# SCHEasyEda.net
KiCad netlist of a schematic drawn in EasyEDA
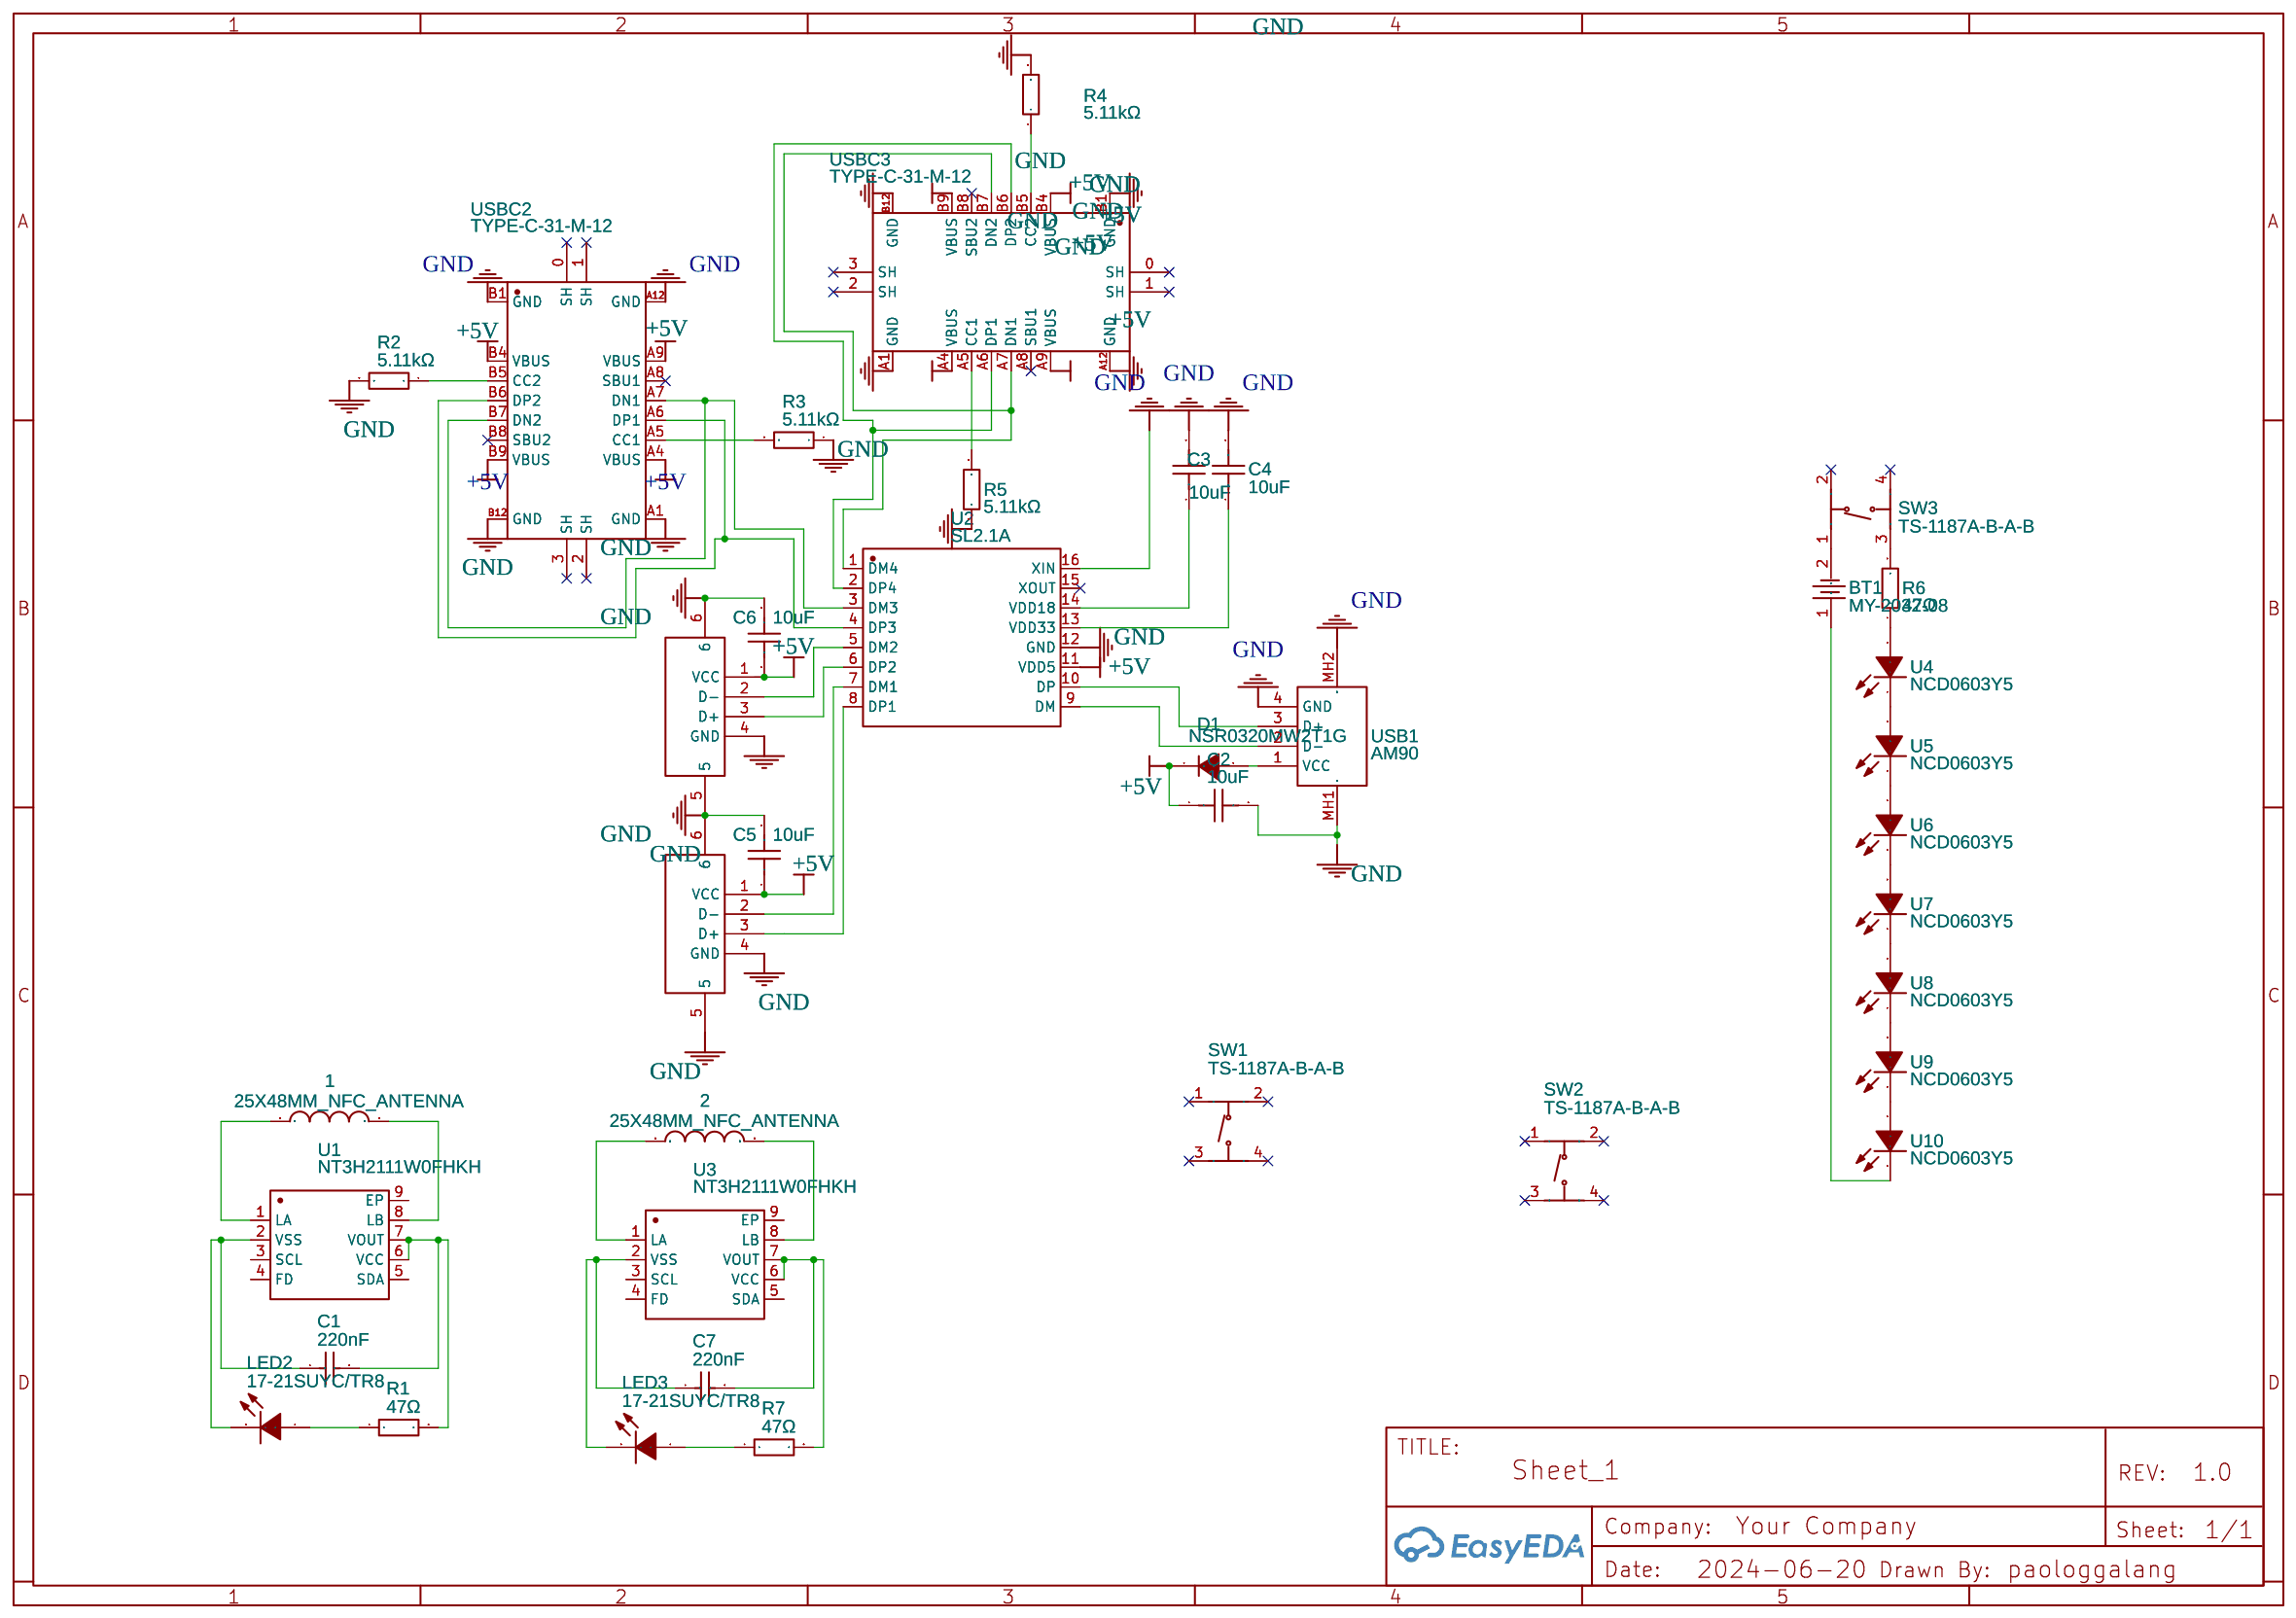
[diagram p0: schematic sheet]

(export (version "E")
  (design (tool "Eeschema 10.0.6"))
  (components
    (comp (ref "1") (value "25X48MM_NFC_ANTENNA") (libsource (lib "") (part "25X48MM_NFC_ANTENNA")))
    (comp (ref "2") (value "25X48MM_NFC_ANTENNA") (libsource (lib "") (part "25X48MM_NFC_ANTENNA")))
    (comp (ref "BT1")
      (value "MY-2032-08")
      (fields (field (name "Manufacturer") "MYOUNG(美阳)"))
      (libsource (lib "") (part "MY-2032-08"))
    )
    (comp (ref "C1")
      (value "220nF")
      (fields
        (field (name "Manufacturer Part") "CL10B224KA8NNNC")
        (field (name "Manufacturer") "SAMSUNG(三星)")
      )
      (libsource (lib "") (part "CL10B224KA8NNNC"))
    )
    (comp (ref "C2")
      (value "10uF")
      (fields
        (field (name "Manufacturer Part") "CL10A106KP8NNNC")
        (field (name "Manufacturer") "SAMSUNG(三星)")
      )
      (libsource (lib "") (part "CL10A106KP8NNNC_1"))
    )
    (comp (ref "C3")
      (value "10uF")
      (fields
        (field (name "Manufacturer Part") "CL10A106KP8NNNC")
        (field (name "Manufacturer") "SAMSUNG(三星)")
      )
      (libsource (lib "") (part "CL10A106KP8NNNC"))
    )
    (comp (ref "C4")
      (value "10uF")
      (fields
        (field (name "Manufacturer Part") "CL10A106KP8NNNC")
        (field (name "Manufacturer") "SAMSUNG(三星)")
      )
      (libsource (lib "") (part "CL10A106KP8NNNC"))
    )
    (comp (ref "C5")
      (value "10uF")
      (fields
        (field (name "Manufacturer Part") "CL10A106KP8NNNC")
        (field (name "Manufacturer") "SAMSUNG(三星)")
      )
      (libsource (lib "") (part "CL10A106KP8NNNC"))
    )
    (comp (ref "C6")
      (value "10uF")
      (fields
        (field (name "Manufacturer Part") "CL10A106KP8NNNC")
        (field (name "Manufacturer") "SAMSUNG(三星)")
      )
      (libsource (lib "") (part "CL10A106KP8NNNC"))
    )
    (comp (ref "C7")
      (value "220nF")
      (fields
        (field (name "Manufacturer Part") "CL10B224KA8NNNC")
        (field (name "Manufacturer") "SAMSUNG(三星)")
      )
      (libsource (lib "") (part "CL10B224KA8NNNC"))
    )
    (comp (ref "D1")
      (value "NSR0320MW2T1G")
      (fields (field (name "Manufacturer") "onsemi(安森美)"))
      (libsource (lib "") (part "NSR0320MW2T1G"))
    )
    (comp (ref "LED2")
      (value "17-21SUYC/TR8")
      (fields (field (name "Manufacturer Part") "KT-0805黄灯") (field (name "Manufacturer") "KENTO"))
      (libsource (lib "") (part "17-21SUYC/TR8"))
    )
    (comp (ref "LED3")
      (value "17-21SUYC/TR8")
      (fields (field (name "Manufacturer Part") "KT-0805黄灯") (field (name "Manufacturer") "KENTO"))
      (libsource (lib "") (part "17-21SUYC/TR8"))
    )
    (comp (ref "R1")
      (value "47Ω")
      (fields
        (field (name "Manufacturer Part") "0603WAF470JT5E")
        (field (name "Manufacturer") "UNI-ROYAL(厚声)")
      )
      (libsource (lib "") (part "0603WAF470JT5E"))
    )
    (comp (ref "R2")
      (value "5.11kΩ")
      (fields
        (field (name "Manufacturer Part") "RMC12065.11K1%N")
        (field (name "Manufacturer") "Tyohm(幸亚电阻)")
      )
      (libsource (lib "") (part "RMC12065.11K1%N"))
    )
    (comp (ref "R3")
      (value "5.11kΩ")
      (fields
        (field (name "Manufacturer Part") "RMC12065.11K1%N")
        (field (name "Manufacturer") "Tyohm(幸亚电阻)")
      )
      (libsource (lib "") (part "RMC12065.11K1%N"))
    )
    (comp (ref "R4")
      (value "5.11kΩ")
      (fields
        (field (name "Manufacturer Part") "RMC12065.11K1%N")
        (field (name "Manufacturer") "Tyohm(幸亚电阻)")
      )
      (libsource (lib "") (part "RMC12065.11K1%N_1"))
    )
    (comp (ref "R5")
      (value "5.11kΩ")
      (fields
        (field (name "Manufacturer Part") "RMC12065.11K1%N")
        (field (name "Manufacturer") "Tyohm(幸亚电阻)")
      )
      (libsource (lib "") (part "RMC12065.11K1%N_1"))
    )
    (comp (ref "R6")
      (value "47Ω")
      (fields
        (field (name "Manufacturer Part") "0603WAF470JT5E")
        (field (name "Manufacturer") "UNI-ROYAL(厚声)")
      )
      (libsource (lib "") (part "0603WAF470JT5E_1"))
    )
    (comp (ref "R7")
      (value "47Ω")
      (fields
        (field (name "Manufacturer Part") "0603WAF470JT5E")
        (field (name "Manufacturer") "UNI-ROYAL(厚声)")
      )
      (libsource (lib "") (part "0603WAF470JT5E"))
    )
    (comp (ref "SW1")
      (value "TS-1187A-B-A-B")
      (fields (field (name "Manufacturer") "XKB Connectivity(中国星坤)"))
      (libsource (lib "") (part "TS-1187A-B-A-B"))
    )
    (comp (ref "SW2")
      (value "TS-1187A-B-A-B")
      (fields (field (name "Manufacturer") "XKB Connectivity(中国星坤)"))
      (libsource (lib "") (part "TS-1187A-B-A-B"))
    )
    (comp (ref "SW3")
      (value "TS-1187A-B-A-B")
      (fields (field (name "Manufacturer") "XKB Connectivity(中国星坤)"))
      (libsource (lib "") (part "TS-1187A-B-A-B_1"))
    )
    (comp (ref "U1")
      (value "NT3H2111W0FHKH")
      (fields (field (name "Manufacturer") "NXP(恩智浦)"))
      (libsource (lib "") (part "NT3H2111W0FHKH"))
    )
    (comp (ref "U2")
      (value "SL2.1A")
      (fields (field (name "Manufacturer") "CoreChips(和芯润德)"))
      (libsource (lib "") (part "SL2.1A"))
    )
    (comp (ref "U3")
      (value "NT3H2111W0FHKH")
      (fields (field (name "Manufacturer") "NXP(恩智浦)"))
      (libsource (lib "") (part "NT3H2111W0FHKH"))
    )
    (comp (ref "U4")
      (value "NCD0603Y5")
      (fields (field (name "Manufacturer") "国星光电"))
      (libsource (lib "") (part "NCD0603Y5"))
    )
    (comp (ref "U5")
      (value "NCD0603Y5")
      (fields (field (name "Manufacturer") "国星光电"))
      (libsource (lib "") (part "NCD0603Y5"))
    )
    (comp (ref "U6")
      (value "NCD0603Y5")
      (fields (field (name "Manufacturer") "国星光电"))
      (libsource (lib "") (part "NCD0603Y5"))
    )
    (comp (ref "U7")
      (value "NCD0603Y5")
      (fields (field (name "Manufacturer") "国星光电"))
      (libsource (lib "") (part "NCD0603Y5"))
    )
    (comp (ref "U8")
      (value "NCD0603Y5")
      (fields (field (name "Manufacturer") "国星光电"))
      (libsource (lib "") (part "NCD0603Y5"))
    )
    (comp (ref "U9")
      (value "NCD0603Y5")
      (fields (field (name "Manufacturer") "国星光电"))
      (libsource (lib "") (part "NCD0603Y5"))
    )
    (comp (ref "U10")
      (value "NCD0603Y5")
      (fields (field (name "Manufacturer") "国星光电"))
      (libsource (lib "") (part "NCD0603Y5"))
    )
    (comp (ref "USB1")
      (value "AM90")
      (fields (field (name "Manufacturer") "SHOU HAN(首韩)"))
      (libsource (lib "") (part "AM90"))
    )
    (comp (ref "USB2")
      (value "USB-AF-90-14.4X13.6-H7.0-DIP")
      (fields (field (name "Manufacturer Part") "903-131A1011D10100") (field (name "Manufacturer") "精拓金"))
      (libsource (lib "") (part "USB-AF-90-14.4X13.6-H7.0-DIP"))
    )
    (comp (ref "USB6")
      (value "USB-AF-90-14.4X13.6-H7.0-DIP")
      (fields (field (name "Manufacturer Part") "903-131A1011D10100") (field (name "Manufacturer") "精拓金"))
      (libsource (lib "") (part "USB-AF-90-14.4X13.6-H7.0-DIP"))
    )
    (comp (ref "USBC2")
      (value "TYPE-C-31-M-12")
      (fields (field (name "Manufacturer") "韩国韩荣"))
      (libsource (lib "") (part "TYPE-C-31-M-12_1"))
    )
    (comp (ref "USBC3")
      (value "TYPE-C-31-M-12")
      (fields (field (name "Manufacturer") "韩国韩荣"))
      (libsource (lib "") (part "TYPE-C-31-M-12"))
    )
  )
  (nets
    (net (code "1") (name "+5V") (class "Default")
      (node (ref "C2") (pin "1") (pinfunction "1_1") (pintype "unspecified"))
      (node (ref "C5") (pin "1") (pinfunction "1_1") (pintype "unspecified"))
      (node (ref "C6") (pin "1") (pinfunction "1_1") (pintype "unspecified"))
      (node (ref "D1") (pin "1") (pinfunction "C_1") (pintype "unspecified"))
      (node (ref "U2") (pin "11") (pinfunction "VDD5_11") (pintype "unspecified"))
      (node (ref "USB2") (pin "1") (pinfunction "VCC_1") (pintype "unspecified"))
      (node (ref "USB6") (pin "1") (pinfunction "VCC_1") (pintype "unspecified"))
      (node (ref "USBC2") (pin "A4") (pinfunction "VBUS_A4") (pintype "unspecified"))
      (node (ref "USBC2") (pin "A9") (pinfunction "VBUS_A9") (pintype "unspecified"))
      (node (ref "USBC2") (pin "B4") (pinfunction "VBUS_B4") (pintype "unspecified"))
      (node (ref "USBC2") (pin "B9") (pinfunction "VBUS_B9") (pintype "unspecified"))
      (node (ref "USBC3") (pin "A4") (pinfunction "VBUS_A4") (pintype "unspecified"))
      (node (ref "USBC3") (pin "A9") (pinfunction "VBUS_A9") (pintype "unspecified"))
      (node (ref "USBC3") (pin "B4") (pinfunction "VBUS_B4") (pintype "unspecified"))
      (node (ref "USBC3") (pin "B9") (pinfunction "VBUS_B9") (pintype "unspecified"))
    )
    (net (code "2") (name "GND") (class "Default")
      (node (ref "C2") (pin "2") (pinfunction "2_2") (pintype "unspecified"))
      (node (ref "C3") (pin "2") (pinfunction "2_2") (pintype "unspecified"))
      (node (ref "C4") (pin "2") (pinfunction "2_2") (pintype "unspecified"))
      (node (ref "C5") (pin "2") (pinfunction "2_2") (pintype "unspecified"))
      (node (ref "C6") (pin "2") (pinfunction "2_2") (pintype "unspecified"))
      (node (ref "R2") (pin "2") (pinfunction "2_2") (pintype "unspecified"))
      (node (ref "R3") (pin "1") (pinfunction "1_1") (pintype "unspecified"))
      (node (ref "R4") (pin "2") (pinfunction "2_2") (pintype "unspecified"))
      (node (ref "R5") (pin "1") (pinfunction "1_1") (pintype "unspecified"))
      (node (ref "U2") (pin "12") (pinfunction "GND_12") (pintype "unspecified"))
      (node (ref "U2") (pin "16") (pinfunction "XIN_16") (pintype "unspecified"))
      (node (ref "USB1") (pin "4") (pinfunction "GND_4") (pintype "input"))
      (node (ref "USB1") (pin "MH1") (pinfunction "MH1_MH1") (pintype "unspecified"))
      (node (ref "USB1") (pin "MH2") (pinfunction "MH2_MH2") (pintype "unspecified"))
      (node (ref "USB2") (pin "4") (pinfunction "GND_4") (pintype "unspecified"))
      (node (ref "USB2") (pin "5") (pinfunction "5_5") (pintype "unspecified"))
      (node (ref "USB2") (pin "6") (pinfunction "6_6") (pintype "unspecified"))
      (node (ref "USB6") (pin "4") (pinfunction "GND_4") (pintype "unspecified"))
      (node (ref "USB6") (pin "5") (pinfunction "5_5") (pintype "unspecified"))
      (node (ref "USB6") (pin "6") (pinfunction "6_6") (pintype "unspecified"))
      (node (ref "USBC2") (pin "A1") (pinfunction "GND_A1") (pintype "unspecified"))
      (node (ref "USBC2") (pin "A12") (pinfunction "GND_A12") (pintype "unspecified"))
      (node (ref "USBC2") (pin "B1") (pinfunction "GND_B1") (pintype "unspecified"))
      (node (ref "USBC2") (pin "B12") (pinfunction "GND_B12") (pintype "unspecified"))
      (node (ref "USBC3") (pin "A1") (pinfunction "GND_A1") (pintype "unspecified"))
      (node (ref "USBC3") (pin "A12") (pinfunction "GND_A12") (pintype "unspecified"))
      (node (ref "USBC3") (pin "B1") (pinfunction "GND_B1") (pintype "unspecified"))
      (node (ref "USBC3") (pin "B12") (pinfunction "GND_B12") (pintype "unspecified"))
    )
    (net (code "3") (name "Net-(D1-A)") (class "Default")
      (node (ref "D1") (pin "2") (pinfunction "A_2") (pintype "unspecified"))
      (node (ref "USB1") (pin "1") (pinfunction "VCC_1") (pintype "input"))
    )
    (net (code "4") (name "Net-(LED2-+)") (class "Default")
      (node (ref "LED2") (pin "1") (pinfunction "+_1") (pintype "unspecified"))
      (node (ref "R1") (pin "1") (pinfunction "1_1") (pintype "input"))
    )
    (net (code "5") (name "Net-(LED2--)") (class "Default")
      (node (ref "C1") (pin "1") (pinfunction "1_1") (pintype "input"))
      (node (ref "LED2") (pin "2") (pinfunction "-_2") (pintype "unspecified"))
      (node (ref "U1") (pin "2") (pinfunction "VSS_2") (pintype "unspecified"))
    )
    (net (code "6") (name "Net-(LED3-+)") (class "Default")
      (node (ref "LED3") (pin "1") (pinfunction "+_1") (pintype "unspecified"))
      (node (ref "R7") (pin "1") (pinfunction "1_1") (pintype "input"))
    )
    (net (code "7") (name "Net-(LED3--)") (class "Default")
      (node (ref "C7") (pin "1") (pinfunction "1_1") (pintype "input"))
      (node (ref "LED3") (pin "2") (pinfunction "-_2") (pintype "unspecified"))
      (node (ref "U3") (pin "2") (pinfunction "VSS_2") (pintype "unspecified"))
    )
    (net (code "8") (name "Net-(SW3-A)") (class "Default")
      (node (ref "BT1") (pin "2") (pinfunction "2_2") (pintype "input"))
      (node (ref "SW3") (pin "1") (pinfunction "A_1") (pintype "unspecified"))
    )
    (net (code "9") (name "Net-(SW3-C)") (class "Default")
      (node (ref "R6") (pin "2") (pinfunction "2_2") (pintype "input"))
      (node (ref "SW3") (pin "3") (pinfunction "C_3") (pintype "unspecified"))
    )
    (net (code "10") (name "Net-(U1-LA)") (class "Default")
      (node (ref "1") (pin "P$1") (pinfunction "P$1_P$1") (pintype "bidirectional"))
      (node (ref "U1") (pin "1") (pinfunction "LA_1") (pintype "unspecified"))
    )
    (net (code "11") (name "Net-(U1-LB)") (class "Default")
      (node (ref "1") (pin "P$2") (pinfunction "P$2_P$2") (pintype "bidirectional"))
      (node (ref "U1") (pin "8") (pinfunction "LB_8") (pintype "unspecified"))
    )
    (net (code "12") (name "Net-(U1-VCC)") (class "Default")
      (node (ref "C1") (pin "2") (pinfunction "2_2") (pintype "input"))
      (node (ref "R1") (pin "2") (pinfunction "2_2") (pintype "input"))
      (node (ref "U1") (pin "6") (pinfunction "VCC_6") (pintype "unspecified"))
      (node (ref "U1") (pin "7") (pinfunction "VOUT_7") (pintype "unspecified"))
    )
    (net (code "13") (name "Net-(U2-DM)") (class "Default")
      (node (ref "U2") (pin "9") (pinfunction "DM_9") (pintype "unspecified"))
      (node (ref "USB1") (pin "2") (pinfunction "D-_2") (pintype "input"))
    )
    (net (code "14") (name "Net-(U2-DM1)") (class "Default")
      (node (ref "U2") (pin "7") (pinfunction "DM1_7") (pintype "unspecified"))
      (node (ref "USB6") (pin "2") (pinfunction "D-_2") (pintype "unspecified"))
    )
    (net (code "15") (name "Net-(U2-DM2)") (class "Default")
      (node (ref "U2") (pin "5") (pinfunction "DM2_5") (pintype "unspecified"))
      (node (ref "USB2") (pin "2") (pinfunction "D-_2") (pintype "unspecified"))
    )
    (net (code "16") (name "Net-(U2-DM3)") (class "Default")
      (node (ref "U2") (pin "3") (pinfunction "DM3_3") (pintype "unspecified"))
      (node (ref "USBC2") (pin "A7") (pinfunction "DN1_A7") (pintype "unspecified"))
      (node (ref "USBC2") (pin "B7") (pinfunction "DN2_B7") (pintype "unspecified"))
    )
    (net (code "17") (name "Net-(U2-DM4)") (class "Default")
      (node (ref "U2") (pin "1") (pinfunction "DM4_1") (pintype "unspecified"))
      (node (ref "USBC3") (pin "A7") (pinfunction "DN1_A7") (pintype "unspecified"))
      (node (ref "USBC3") (pin "B7") (pinfunction "DN2_B7") (pintype "unspecified"))
    )
    (net (code "18") (name "Net-(U2-DP)") (class "Default")
      (node (ref "U2") (pin "10") (pinfunction "DP_10") (pintype "unspecified"))
      (node (ref "USB1") (pin "3") (pinfunction "D+_3") (pintype "input"))
    )
    (net (code "19") (name "Net-(U2-DP1)") (class "Default")
      (node (ref "U2") (pin "8") (pinfunction "DP1_8") (pintype "unspecified"))
      (node (ref "USB6") (pin "3") (pinfunction "D+_3") (pintype "unspecified"))
    )
    (net (code "20") (name "Net-(U2-DP2)") (class "Default")
      (node (ref "U2") (pin "6") (pinfunction "DP2_6") (pintype "unspecified"))
      (node (ref "USB2") (pin "3") (pinfunction "D+_3") (pintype "unspecified"))
    )
    (net (code "21") (name "Net-(U2-DP3)") (class "Default")
      (node (ref "U2") (pin "4") (pinfunction "DP3_4") (pintype "unspecified"))
      (node (ref "USBC2") (pin "A6") (pinfunction "DP1_A6") (pintype "unspecified"))
      (node (ref "USBC2") (pin "B6") (pinfunction "DP2_B6") (pintype "unspecified"))
    )
    (net (code "22") (name "Net-(U2-DP4)") (class "Default")
      (node (ref "U2") (pin "2") (pinfunction "DP4_2") (pintype "unspecified"))
      (node (ref "USBC3") (pin "A6") (pinfunction "DP1_A6") (pintype "unspecified"))
      (node (ref "USBC3") (pin "B6") (pinfunction "DP2_B6") (pintype "unspecified"))
    )
    (net (code "23") (name "Net-(U2-VDD18)") (class "Default")
      (node (ref "C3") (pin "1") (pinfunction "1_1") (pintype "unspecified"))
      (node (ref "U2") (pin "14") (pinfunction "VDD18_14") (pintype "unspecified"))
    )
    (net (code "24") (name "Net-(U2-VDD33)") (class "Default")
      (node (ref "C4") (pin "1") (pinfunction "1_1") (pintype "unspecified"))
      (node (ref "U2") (pin "13") (pinfunction "VDD33_13") (pintype "unspecified"))
    )
    (net (code "25") (name "Net-(U3-LA)") (class "Default")
      (node (ref "2") (pin "P$1") (pinfunction "P$1_P$1") (pintype "bidirectional"))
      (node (ref "U3") (pin "1") (pinfunction "LA_1") (pintype "unspecified"))
    )
    (net (code "26") (name "Net-(U3-LB)") (class "Default")
      (node (ref "2") (pin "P$2") (pinfunction "P$2_P$2") (pintype "bidirectional"))
      (node (ref "U3") (pin "8") (pinfunction "LB_8") (pintype "unspecified"))
    )
    (net (code "27") (name "Net-(U3-VCC)") (class "Default")
      (node (ref "C7") (pin "2") (pinfunction "2_2") (pintype "input"))
      (node (ref "R7") (pin "2") (pinfunction "2_2") (pintype "input"))
      (node (ref "U3") (pin "6") (pinfunction "VCC_6") (pintype "unspecified"))
      (node (ref "U3") (pin "7") (pinfunction "VOUT_7") (pintype "unspecified"))
    )
    (net (code "28") (name "Net-(U4-+)") (class "Default")
      (node (ref "R6") (pin "1") (pinfunction "1_1") (pintype "input"))
      (node (ref "U4") (pin "2") (pinfunction "+_2") (pintype "unspecified"))
    )
    (net (code "29") (name "Net-(U4--)") (class "Default")
      (node (ref "U4") (pin "1") (pinfunction "-_1") (pintype "unspecified"))
      (node (ref "U5") (pin "2") (pinfunction "+_2") (pintype "unspecified"))
    )
    (net (code "30") (name "Net-(U5--)") (class "Default")
      (node (ref "U5") (pin "1") (pinfunction "-_1") (pintype "unspecified"))
      (node (ref "U6") (pin "2") (pinfunction "+_2") (pintype "unspecified"))
    )
    (net (code "31") (name "Net-(U6--)") (class "Default")
      (node (ref "U6") (pin "1") (pinfunction "-_1") (pintype "unspecified"))
      (node (ref "U7") (pin "2") (pinfunction "+_2") (pintype "unspecified"))
    )
    (net (code "32") (name "Net-(U7--)") (class "Default")
      (node (ref "U7") (pin "1") (pinfunction "-_1") (pintype "unspecified"))
      (node (ref "U8") (pin "2") (pinfunction "+_2") (pintype "unspecified"))
    )
    (net (code "33") (name "Net-(U8--)") (class "Default")
      (node (ref "U8") (pin "1") (pinfunction "-_1") (pintype "unspecified"))
      (node (ref "U9") (pin "2") (pinfunction "+_2") (pintype "unspecified"))
    )
    (net (code "34") (name "Net-(U10-+)") (class "Default")
      (node (ref "U10") (pin "2") (pinfunction "+_2") (pintype "unspecified"))
      (node (ref "U9") (pin "1") (pinfunction "-_1") (pintype "unspecified"))
    )
    (net (code "35") (name "Net-(U10--)") (class "Default")
      (node (ref "BT1") (pin "1") (pinfunction "1_1") (pintype "input"))
      (node (ref "U10") (pin "1") (pinfunction "-_1") (pintype "unspecified"))
    )
    (net (code "36") (name "Net-(USBC2-CC1)") (class "Default")
      (node (ref "R3") (pin "2") (pinfunction "2_2") (pintype "unspecified"))
      (node (ref "USBC2") (pin "A5") (pinfunction "CC1_A5") (pintype "unspecified"))
    )
    (net (code "37") (name "Net-(USBC2-CC2)") (class "Default")
      (node (ref "R2") (pin "1") (pinfunction "1_1") (pintype "unspecified"))
      (node (ref "USBC2") (pin "B5") (pinfunction "CC2_B5") (pintype "unspecified"))
    )
    (net (code "38") (name "Net-(USBC3-CC1)") (class "Default")
      (node (ref "R5") (pin "2") (pinfunction "2_2") (pintype "unspecified"))
      (node (ref "USBC3") (pin "A5") (pinfunction "CC1_A5") (pintype "unspecified"))
    )
    (net (code "39") (name "Net-(USBC3-CC2)") (class "Default")
      (node (ref "R4") (pin "1") (pinfunction "1_1") (pintype "unspecified"))
      (node (ref "USBC3") (pin "B5") (pinfunction "CC2_B5") (pintype "unspecified"))
    )
    (net (code "40") (name "unconnected-(SW1-A-Pad1)") (class "Default")
      (node (ref "SW1") (pin "1") (pinfunction "A_1") (pintype "unspecified+no_connect"))
    )
    (net (code "41") (name "unconnected-(SW1-B-Pad2)") (class "Default")
      (node (ref "SW1") (pin "2") (pinfunction "B_2") (pintype "unspecified+no_connect"))
    )
    (net (code "42") (name "unconnected-(SW1-C-Pad3)") (class "Default")
      (node (ref "SW1") (pin "3") (pinfunction "C_3") (pintype "unspecified+no_connect"))
    )
    (net (code "43") (name "unconnected-(SW1-D-Pad4)") (class "Default")
      (node (ref "SW1") (pin "4") (pinfunction "D_4") (pintype "unspecified+no_connect"))
    )
    (net (code "44") (name "unconnected-(SW2-A-Pad1)") (class "Default")
      (node (ref "SW2") (pin "1") (pinfunction "A_1") (pintype "unspecified+no_connect"))
    )
    (net (code "45") (name "unconnected-(SW2-B-Pad2)") (class "Default")
      (node (ref "SW2") (pin "2") (pinfunction "B_2") (pintype "unspecified+no_connect"))
    )
    (net (code "46") (name "unconnected-(SW2-C-Pad3)") (class "Default")
      (node (ref "SW2") (pin "3") (pinfunction "C_3") (pintype "unspecified+no_connect"))
    )
    (net (code "47") (name "unconnected-(SW2-D-Pad4)") (class "Default")
      (node (ref "SW2") (pin "4") (pinfunction "D_4") (pintype "unspecified+no_connect"))
    )
    (net (code "48") (name "unconnected-(SW3-B-Pad2)") (class "Default")
      (node (ref "SW3") (pin "2") (pinfunction "B_2") (pintype "unspecified+no_connect"))
    )
    (net (code "49") (name "unconnected-(SW3-D-Pad4)") (class "Default")
      (node (ref "SW3") (pin "4") (pinfunction "D_4") (pintype "unspecified+no_connect"))
    )
    (net (code "50") (name "unconnected-(U1-EP-Pad9)") (class "Default")
      (node (ref "U1") (pin "9") (pinfunction "EP_9") (pintype "unspecified"))
    )
    (net (code "51") (name "unconnected-(U1-FD-Pad4)") (class "Default")
      (node (ref "U1") (pin "4") (pinfunction "FD_4") (pintype "unspecified"))
    )
    (net (code "52") (name "unconnected-(U1-SCL-Pad3)") (class "Default")
      (node (ref "U1") (pin "3") (pinfunction "SCL_3") (pintype "unspecified"))
    )
    (net (code "53") (name "unconnected-(U1-SDA-Pad5)") (class "Default")
      (node (ref "U1") (pin "5") (pinfunction "SDA_5") (pintype "unspecified"))
    )
    (net (code "54") (name "unconnected-(U2-XOUT-Pad15)") (class "Default")
      (node (ref "U2") (pin "15") (pinfunction "XOUT_15") (pintype "unspecified+no_connect"))
    )
    (net (code "55") (name "unconnected-(U3-EP-Pad9)") (class "Default")
      (node (ref "U3") (pin "9") (pinfunction "EP_9") (pintype "unspecified"))
    )
    (net (code "56") (name "unconnected-(U3-FD-Pad4)") (class "Default")
      (node (ref "U3") (pin "4") (pinfunction "FD_4") (pintype "unspecified"))
    )
    (net (code "57") (name "unconnected-(U3-SCL-Pad3)") (class "Default")
      (node (ref "U3") (pin "3") (pinfunction "SCL_3") (pintype "unspecified"))
    )
    (net (code "58") (name "unconnected-(U3-SDA-Pad5)") (class "Default")
      (node (ref "U3") (pin "5") (pinfunction "SDA_5") (pintype "unspecified"))
    )
    (net (code "59") (name "unconnected-(USBC2-SBU1-PadA8)") (class "Default")
      (node (ref "USBC2") (pin "A8") (pinfunction "SBU1_A8") (pintype "unspecified+no_connect"))
    )
    (net (code "60") (name "unconnected-(USBC2-SBU2-PadB8)") (class "Default")
      (node (ref "USBC2") (pin "B8") (pinfunction "SBU2_B8") (pintype "unspecified+no_connect"))
    )
    (net (code "61") (name "unconnected-(USBC2-SH-Pad0)") (class "Default")
      (node (ref "USBC2") (pin "0") (pinfunction "SH_0") (pintype "unspecified+no_connect"))
    )
    (net (code "62") (name "unconnected-(USBC2-SH-Pad1)") (class "Default")
      (node (ref "USBC2") (pin "1") (pinfunction "SH_1") (pintype "unspecified+no_connect"))
    )
    (net (code "63") (name "unconnected-(USBC2-SH-Pad2)") (class "Default")
      (node (ref "USBC2") (pin "2") (pinfunction "SH_2") (pintype "unspecified+no_connect"))
    )
    (net (code "64") (name "unconnected-(USBC2-SH-Pad3)") (class "Default")
      (node (ref "USBC2") (pin "3") (pinfunction "SH_3") (pintype "unspecified+no_connect"))
    )
    (net (code "65") (name "unconnected-(USBC3-SBU1-PadA8)") (class "Default")
      (node (ref "USBC3") (pin "A8") (pinfunction "SBU1_A8") (pintype "unspecified+no_connect"))
    )
    (net (code "66") (name "unconnected-(USBC3-SBU2-PadB8)") (class "Default")
      (node (ref "USBC3") (pin "B8") (pinfunction "SBU2_B8") (pintype "unspecified+no_connect"))
    )
    (net (code "67") (name "unconnected-(USBC3-SH-Pad0)") (class "Default")
      (node (ref "USBC3") (pin "0") (pinfunction "SH_0") (pintype "unspecified+no_connect"))
    )
    (net (code "68") (name "unconnected-(USBC3-SH-Pad1)") (class "Default")
      (node (ref "USBC3") (pin "1") (pinfunction "SH_1") (pintype "unspecified+no_connect"))
    )
    (net (code "69") (name "unconnected-(USBC3-SH-Pad2)") (class "Default")
      (node (ref "USBC3") (pin "2") (pinfunction "SH_2") (pintype "unspecified+no_connect"))
    )
    (net (code "70") (name "unconnected-(USBC3-SH-Pad3)") (class "Default")
      (node (ref "USBC3") (pin "3") (pinfunction "SH_3") (pintype "unspecified+no_connect"))
    )
  )
)
